# rs485.net
KiCad netlist of a schematic drawn in EAGLE
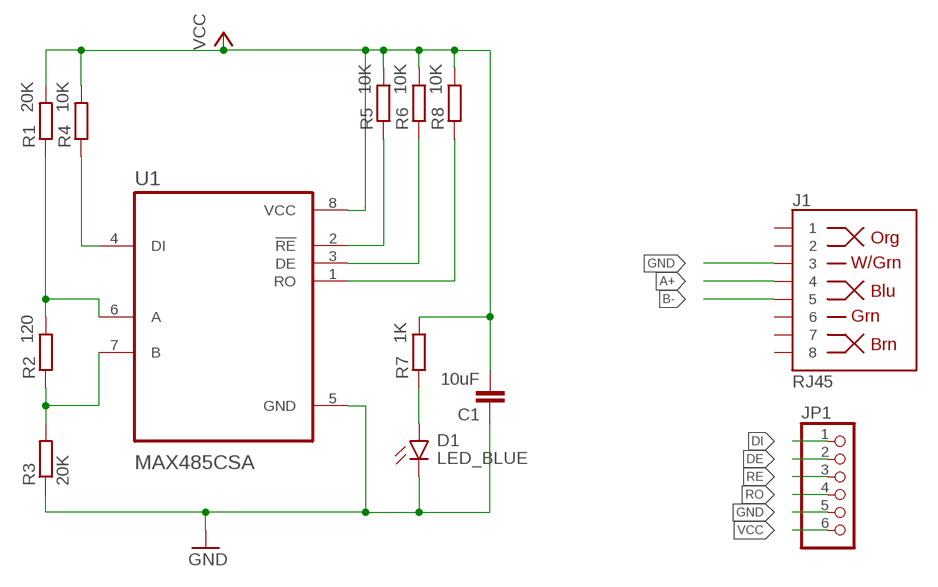
[diagram p0: schematic, sheet 1]

(export (version "E")
  (design (tool "Eeschema 10.0.6"))
  (components
    (comp (ref "C1")
      (value "10uF")
      (footprint "eagle-import:C1206")
      (libsource (lib "eagle-import") (part "C-EUC1206"))
    )
    (comp (ref "D1")
      (value "LED_BLUE")
      (footprint "eagle-import:LEDC3216X75N_FLAT-B")
      (libsource (lib "eagle-import") (part "CHIP-FLAT-B_1206"))
    )
    (comp (ref "J1")
      (value "RJ45")
      (footprint "eagle-import:RJ45-8")
      (libsource (lib "eagle-import") (part "RJ45-8"))
    )
    (comp (ref "JP1")
      (value "PINHD-1X6")
      (footprint "eagle-import:1X06")
      (libsource (lib "eagle-import") (part "PINHD-1X6"))
    )
    (comp (ref "R1")
      (value "20K")
      (footprint "eagle-import:M1406")
      (libsource (lib "eagle-import") (part "R-EU_M1406"))
    )
    (comp (ref "R2")
      (value "120")
      (footprint "eagle-import:M1406")
      (libsource (lib "eagle-import") (part "R-EU_M1406"))
    )
    (comp (ref "R3")
      (value "20K")
      (footprint "eagle-import:M1406")
      (libsource (lib "eagle-import") (part "R-EU_M1406"))
    )
    (comp (ref "R4")
      (value "10K")
      (footprint "eagle-import:M1406")
      (libsource (lib "eagle-import") (part "R-EU_M1406"))
    )
    (comp (ref "R5")
      (value "10K")
      (footprint "eagle-import:M1406")
      (libsource (lib "eagle-import") (part "R-EU_M1406"))
    )
    (comp (ref "R6")
      (value "10K")
      (footprint "eagle-import:M1406")
      (libsource (lib "eagle-import") (part "R-EU_M1406"))
    )
    (comp (ref "R7")
      (value "1K")
      (footprint "eagle-import:M1406")
      (libsource (lib "eagle-import") (part "R-EU_M1406"))
    )
    (comp (ref "R8")
      (value "10K")
      (footprint "eagle-import:M1406")
      (libsource (lib "eagle-import") (part "R-EU_M1406"))
    )
    (comp (ref "U1")
      (value "MAX485CSA")
      (footprint "eagle-import:SOIC127P600X175-8N")
      (fields (field (name "DIGI-KEY_PART_NUMBER") "MAX485CSA-ND") (field (name "MF") "Maxim Integrated"))
      (libsource (lib "eagle-import") (part "MAX485CSA"))
    )
  )
  (nets
    (net (code "1") (name "A+") (class "Default")
      (node (ref "J1") (pin "4") (pinfunction "4_4") (pintype "bidirectional"))
      (node (ref "R1") (pin "1") (pinfunction "1_1") (pintype "passive"))
      (node (ref "R2") (pin "2") (pinfunction "2_2") (pintype "passive"))
      (node (ref "U1") (pin "6") (pinfunction "A_6") (pintype "bidirectional"))
    )
    (net (code "2") (name "B-") (class "Default")
      (node (ref "J1") (pin "5") (pinfunction "5_5") (pintype "bidirectional"))
      (node (ref "R2") (pin "1") (pinfunction "1_1") (pintype "passive"))
      (node (ref "R3") (pin "2") (pinfunction "2_2") (pintype "passive"))
      (node (ref "U1") (pin "7") (pinfunction "B_7") (pintype "bidirectional"))
    )
    (net (code "3") (name "DE") (class "Default")
      (node (ref "JP1") (pin "2") (pinfunction "2_2") (pintype "passive"))
      (node (ref "R6") (pin "1") (pinfunction "1_1") (pintype "passive"))
      (node (ref "U1") (pin "3") (pinfunction "DE_3") (pintype "output"))
    )
    (net (code "4") (name "DI") (class "Default")
      (node (ref "JP1") (pin "1") (pinfunction "1_1") (pintype "passive"))
      (node (ref "R4") (pin "1") (pinfunction "1_1") (pintype "passive"))
      (node (ref "U1") (pin "4") (pinfunction "DI_4") (pintype "input"))
    )
    (net (code "5") (name "GND") (class "Default")
      (node (ref "C1") (pin "1") (pinfunction "1_1") (pintype "passive"))
      (node (ref "D1") (pin "C") (pinfunction "C_C") (pintype "passive"))
      (node (ref "J1") (pin "3") (pinfunction "3_3") (pintype "bidirectional"))
      (node (ref "JP1") (pin "5") (pinfunction "5_5") (pintype "passive"))
      (node (ref "R3") (pin "1") (pinfunction "1_1") (pintype "passive"))
      (node (ref "U1") (pin "5") (pinfunction "GND_5") (pintype "power_in"))
    )
    (net (code "6") (name "Net-(D1-PadA)") (class "Default")
      (node (ref "D1") (pin "A") (pinfunction "A_A") (pintype "passive"))
      (node (ref "R7") (pin "1") (pinfunction "1_1") (pintype "passive"))
    )
    (net (code "7") (name "RE") (class "Default")
      (node (ref "JP1") (pin "3") (pinfunction "3_3") (pintype "passive"))
      (node (ref "R5") (pin "1") (pinfunction "1_1") (pintype "passive"))
      (node (ref "U1") (pin "2") (pinfunction "~{RE}_2") (pintype "output"))
    )
    (net (code "8") (name "RO") (class "Default")
      (node (ref "JP1") (pin "4") (pinfunction "4_4") (pintype "passive"))
      (node (ref "R8") (pin "1") (pinfunction "1_1") (pintype "passive"))
      (node (ref "U1") (pin "1") (pinfunction "RO_1") (pintype "output"))
    )
    (net (code "9") (name "VCC") (class "Default")
      (node (ref "C1") (pin "2") (pinfunction "2_2") (pintype "passive"))
      (node (ref "JP1") (pin "6") (pinfunction "6_6") (pintype "passive"))
      (node (ref "R1") (pin "2") (pinfunction "2_2") (pintype "passive"))
      (node (ref "R4") (pin "2") (pinfunction "2_2") (pintype "passive"))
      (node (ref "R5") (pin "2") (pinfunction "2_2") (pintype "passive"))
      (node (ref "R6") (pin "2") (pinfunction "2_2") (pintype "passive"))
      (node (ref "R7") (pin "2") (pinfunction "2_2") (pintype "passive"))
      (node (ref "R8") (pin "2") (pinfunction "2_2") (pintype "passive"))
      (node (ref "U1") (pin "8") (pinfunction "VCC_8") (pintype "power_in"))
    )
    (net (code "10") (name "unconnected-(J1-Pad1)") (class "Default")
      (node (ref "J1") (pin "1") (pinfunction "1_1") (pintype "bidirectional"))
    )
    (net (code "11") (name "unconnected-(J1-Pad2)") (class "Default")
      (node (ref "J1") (pin "2") (pinfunction "2_2") (pintype "bidirectional"))
    )
    (net (code "12") (name "unconnected-(J1-Pad6)") (class "Default")
      (node (ref "J1") (pin "6") (pinfunction "6_6") (pintype "bidirectional"))
    )
    (net (code "13") (name "unconnected-(J1-Pad7)") (class "Default")
      (node (ref "J1") (pin "7") (pinfunction "7_7") (pintype "bidirectional"))
    )
    (net (code "14") (name "unconnected-(J1-Pad8)") (class "Default")
      (node (ref "J1") (pin "8") (pinfunction "8_8") (pintype "bidirectional"))
    )
  )
)
